# clock.net
KiCad netlist of a schematic drawn in EAGLE
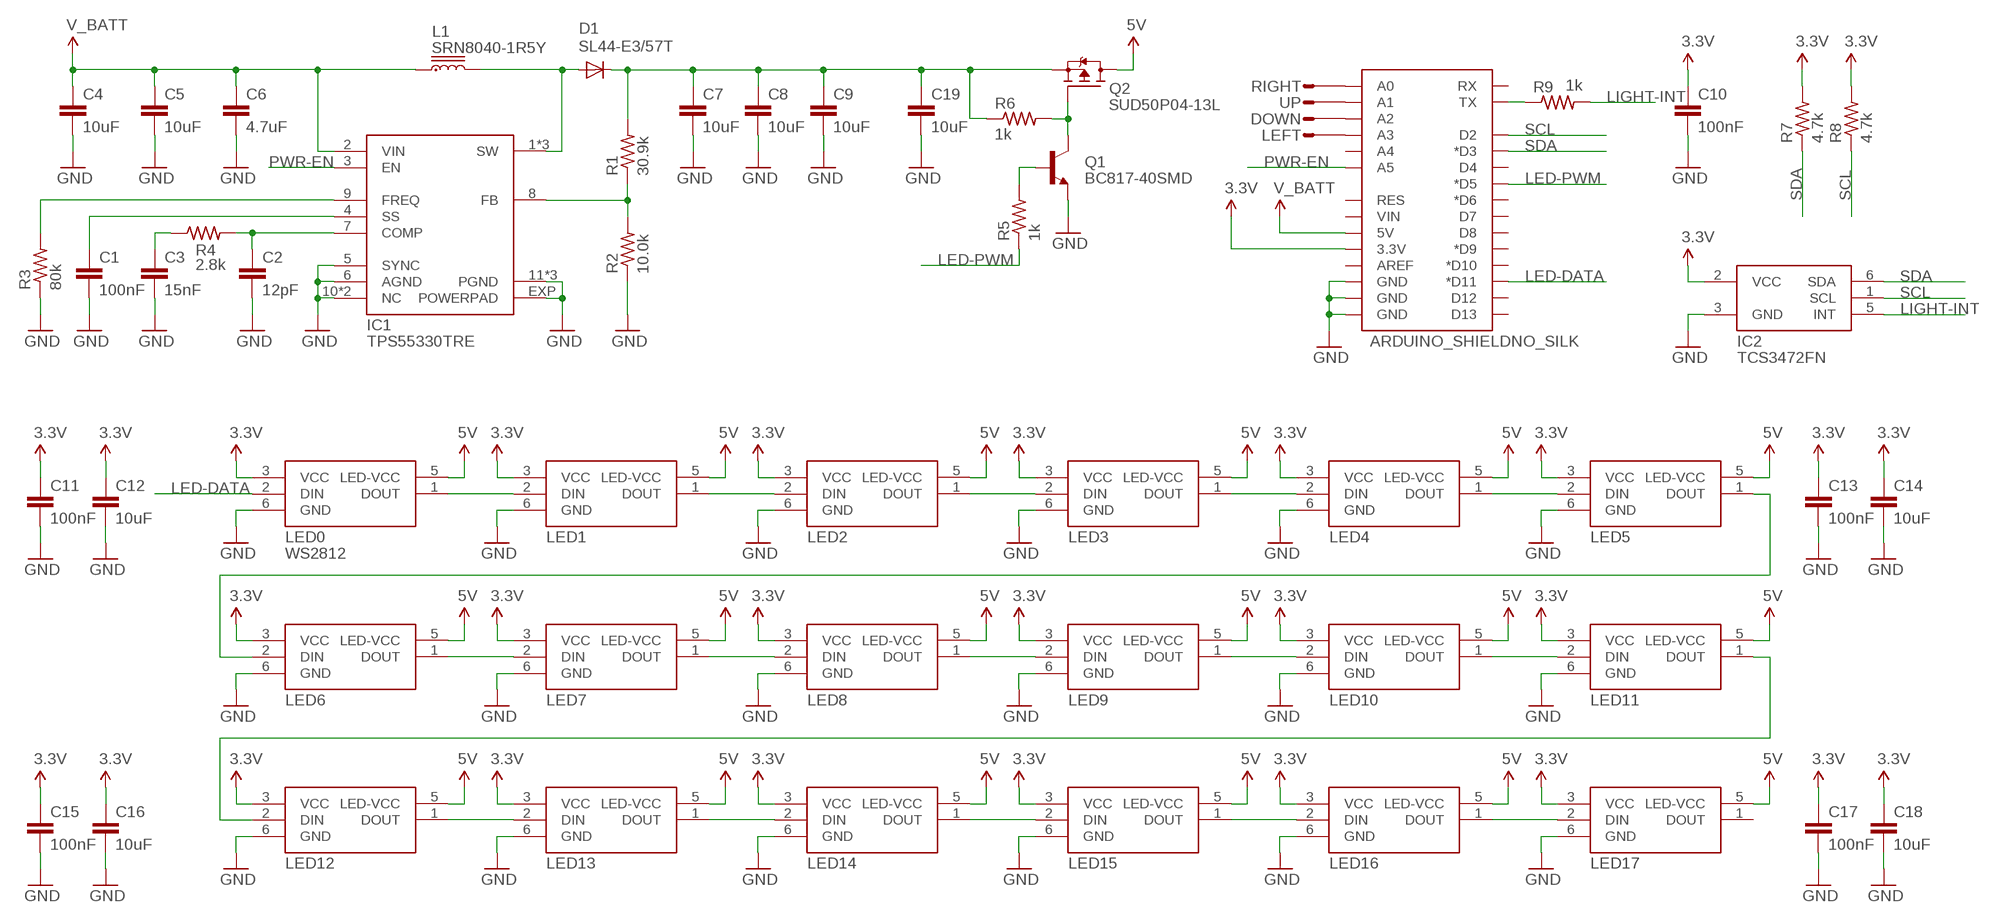
[diagram p0: schematic, sheet 1]

(export (version "E")
  (design (tool "Eeschema 10.0.6"))
  (components
    (comp (ref "C1")
      (value "100nF")
      (footprint "eagle-import:C0603K")
      (libsource (lib "eagle-import") (part "C-EUC0603K"))
    )
    (comp (ref "C2")
      (value "12pF")
      (footprint "eagle-import:C0603K")
      (libsource (lib "eagle-import") (part "C-EUC0603K"))
    )
    (comp (ref "C3")
      (value "15nF")
      (footprint "eagle-import:C0603K")
      (libsource (lib "eagle-import") (part "C-EUC0603K"))
    )
    (comp (ref "C4")
      (value "10uF")
      (footprint "eagle-import:C1206K")
      (libsource (lib "eagle-import") (part "C-EUC1206K"))
    )
    (comp (ref "C5")
      (value "10uF")
      (footprint "eagle-import:C1206K")
      (libsource (lib "eagle-import") (part "C-EUC1206K"))
    )
    (comp (ref "C6")
      (value "4.7uF")
      (footprint "eagle-import:C0805K")
      (libsource (lib "eagle-import") (part "C-EUC0805K"))
    )
    (comp (ref "C7")
      (value "10uF")
      (footprint "eagle-import:C1206K")
      (libsource (lib "eagle-import") (part "C-EUC1206K"))
    )
    (comp (ref "C8")
      (value "10uF")
      (footprint "eagle-import:C1206K")
      (libsource (lib "eagle-import") (part "C-EUC1206K"))
    )
    (comp (ref "C9")
      (value "10uF")
      (footprint "eagle-import:C1206K")
      (libsource (lib "eagle-import") (part "C-EUC1206K"))
    )
    (comp (ref "C10")
      (value "100nF")
      (footprint "eagle-import:C0603K")
      (libsource (lib "eagle-import") (part "C-EUC0603K"))
    )
    (comp (ref "C11")
      (value "100nF")
      (footprint "eagle-import:C0603K")
      (libsource (lib "eagle-import") (part "C-EUC0603K"))
    )
    (comp (ref "C12")
      (value "10uF")
      (footprint "eagle-import:C1206K")
      (libsource (lib "eagle-import") (part "C-EUC1206K"))
    )
    (comp (ref "C13")
      (value "100nF")
      (footprint "eagle-import:C0603K")
      (libsource (lib "eagle-import") (part "C-EUC0603K"))
    )
    (comp (ref "C14")
      (value "10uF")
      (footprint "eagle-import:C1206K")
      (libsource (lib "eagle-import") (part "C-EUC1206K"))
    )
    (comp (ref "C15")
      (value "100nF")
      (footprint "eagle-import:C0603K")
      (libsource (lib "eagle-import") (part "C-EUC0603K"))
    )
    (comp (ref "C16")
      (value "10uF")
      (footprint "eagle-import:C1206K")
      (libsource (lib "eagle-import") (part "C-EUC1206K"))
    )
    (comp (ref "C17")
      (value "100nF")
      (footprint "eagle-import:C0603K")
      (libsource (lib "eagle-import") (part "C-EUC0603K"))
    )
    (comp (ref "C18")
      (value "10uF")
      (footprint "eagle-import:C1206K")
      (libsource (lib "eagle-import") (part "C-EUC1206K"))
    )
    (comp (ref "C19")
      (value "10uF")
      (footprint "eagle-import:C1206K")
      (libsource (lib "eagle-import") (part "C-EUC1206K"))
    )
    (comp (ref "CN1")
      (value "ARDUINO_SHIELDNO_SILK")
      (footprint "eagle-import:DUEMILANOVE_VIAS")
      (libsource (lib "eagle-import") (part "ARDUINO_SHIELDNO_SILK"))
    )
    (comp (ref "D1")
      (value "SL44-E3/57T")
      (footprint "eagle-import:SMC")
      (libsource (lib "eagle-import") (part "DIODE-SMC"))
    )
    (comp (ref "DOWN")
      (value "CAP-PAD15MM")
      (footprint "eagle-import:CAP-PAD-15MM")
      (libsource (lib "eagle-import") (part "CAP-PAD15MM"))
    )
    (comp (ref "IC1")
      (value "TPS55330TRE")
      (footprint "eagle-import:QFN16")
      (libsource (lib "eagle-import") (part "TPS55330TRE"))
    )
    (comp (ref "IC2")
      (value "TCS3472FN")
      (footprint "eagle-import:DFN-6")
      (libsource (lib "eagle-import") (part "TCS3472FN"))
    )
    (comp (ref "L1")
      (value "SRN8040-1R5Y")
      (footprint "eagle-import:SRN8040")
      (libsource (lib "eagle-import") (part "SRN8040"))
    )
    (comp (ref "LED0")
      (value "WS2812")
      (footprint "eagle-import:LED-TRICOLOR-5050-IC")
      (libsource (lib "eagle-import") (part "WS2812"))
    )
    (comp (ref "LED1")
      (value "WS2812")
      (footprint "eagle-import:LED-TRICOLOR-5050-IC")
      (libsource (lib "eagle-import") (part "WS2812"))
    )
    (comp (ref "LED2")
      (value "WS2812")
      (footprint "eagle-import:LED-TRICOLOR-5050-IC")
      (libsource (lib "eagle-import") (part "WS2812"))
    )
    (comp (ref "LED3")
      (value "WS2812")
      (footprint "eagle-import:LED-TRICOLOR-5050-IC")
      (libsource (lib "eagle-import") (part "WS2812"))
    )
    (comp (ref "LED4")
      (value "WS2812")
      (footprint "eagle-import:LED-TRICOLOR-5050-IC")
      (libsource (lib "eagle-import") (part "WS2812"))
    )
    (comp (ref "LED5")
      (value "WS2812")
      (footprint "eagle-import:LED-TRICOLOR-5050-IC")
      (libsource (lib "eagle-import") (part "WS2812"))
    )
    (comp (ref "LED6")
      (value "WS2812")
      (footprint "eagle-import:LED-TRICOLOR-5050-IC")
      (libsource (lib "eagle-import") (part "WS2812"))
    )
    (comp (ref "LED7")
      (value "WS2812")
      (footprint "eagle-import:LED-TRICOLOR-5050-IC")
      (libsource (lib "eagle-import") (part "WS2812"))
    )
    (comp (ref "LED8")
      (value "WS2812")
      (footprint "eagle-import:LED-TRICOLOR-5050-IC")
      (libsource (lib "eagle-import") (part "WS2812"))
    )
    (comp (ref "LED9")
      (value "WS2812")
      (footprint "eagle-import:LED-TRICOLOR-5050-IC")
      (libsource (lib "eagle-import") (part "WS2812"))
    )
    (comp (ref "LED10")
      (value "WS2812")
      (footprint "eagle-import:LED-TRICOLOR-5050-IC")
      (libsource (lib "eagle-import") (part "WS2812"))
    )
    (comp (ref "LED11")
      (value "WS2812")
      (footprint "eagle-import:LED-TRICOLOR-5050-IC")
      (libsource (lib "eagle-import") (part "WS2812"))
    )
    (comp (ref "LED12")
      (value "WS2812")
      (footprint "eagle-import:LED-TRICOLOR-5050-IC")
      (libsource (lib "eagle-import") (part "WS2812"))
    )
    (comp (ref "LED13")
      (value "WS2812")
      (footprint "eagle-import:LED-TRICOLOR-5050-IC")
      (libsource (lib "eagle-import") (part "WS2812"))
    )
    (comp (ref "LED14")
      (value "WS2812")
      (footprint "eagle-import:LED-TRICOLOR-5050-IC")
      (libsource (lib "eagle-import") (part "WS2812"))
    )
    (comp (ref "LED15")
      (value "WS2812")
      (footprint "eagle-import:LED-TRICOLOR-5050-IC")
      (libsource (lib "eagle-import") (part "WS2812"))
    )
    (comp (ref "LED16")
      (value "WS2812")
      (footprint "eagle-import:LED-TRICOLOR-5050-IC")
      (libsource (lib "eagle-import") (part "WS2812"))
    )
    (comp (ref "LED17")
      (value "WS2812")
      (footprint "eagle-import:LED-TRICOLOR-5050-IC")
      (libsource (lib "eagle-import") (part "WS2812"))
    )
    (comp (ref "LEFT")
      (value "CAP-PAD15MM")
      (footprint "eagle-import:CAP-PAD-15MM")
      (libsource (lib "eagle-import") (part "CAP-PAD15MM"))
    )
    (comp (ref "Q1")
      (value "BC817-40SMD")
      (footprint "eagle-import:SOT23-BEC")
      (libsource (lib "eagle-import") (part "BC817SMD-40"))
    )
    (comp (ref "Q2")
      (value "SUD50P04-13L")
      (footprint "eagle-import:TO252")
      (libsource (lib "eagle-import") (part "FDD4141TO252"))
    )
    (comp (ref "R1")
      (value "30.9k")
      (footprint "eagle-import:R0603")
      (libsource (lib "eagle-import") (part "R-US_R0603"))
    )
    (comp (ref "R2")
      (value "10.0k")
      (footprint "eagle-import:R0603")
      (libsource (lib "eagle-import") (part "R-US_R0603"))
    )
    (comp (ref "R3")
      (value "80k")
      (footprint "eagle-import:R0603")
      (libsource (lib "eagle-import") (part "R-US_R0603"))
    )
    (comp (ref "R4")
      (value "2.8k")
      (footprint "eagle-import:R0603")
      (libsource (lib "eagle-import") (part "R-US_R0603"))
    )
    (comp (ref "R5")
      (value "1k")
      (footprint "eagle-import:R0603")
      (libsource (lib "eagle-import") (part "R-US_R0603"))
    )
    (comp (ref "R6")
      (value "1k")
      (footprint "eagle-import:R0603")
      (libsource (lib "eagle-import") (part "R-US_R0603"))
    )
    (comp (ref "R7")
      (value "4.7k")
      (footprint "eagle-import:R0603")
      (libsource (lib "eagle-import") (part "R-US_R0603"))
    )
    (comp (ref "R8")
      (value "4.7k")
      (footprint "eagle-import:R0603")
      (libsource (lib "eagle-import") (part "R-US_R0603"))
    )
    (comp (ref "R9")
      (value "1k")
      (footprint "eagle-import:R0603")
      (libsource (lib "eagle-import") (part "R-US_R0603"))
    )
    (comp (ref "RIGHT")
      (value "CAP-PAD15MM")
      (footprint "eagle-import:CAP-PAD-15MM")
      (libsource (lib "eagle-import") (part "CAP-PAD15MM"))
    )
    (comp (ref "UP")
      (value "CAP-PAD15MM")
      (footprint "eagle-import:CAP-PAD-15MM")
      (libsource (lib "eagle-import") (part "CAP-PAD15MM"))
    )
  )
  (nets
    (net (code "1") (name "/LED-DATA") (class "Default")
      (node (ref "CN1") (pin "D11") (pinfunction "*D11_D11") (pintype "bidirectional"))
      (node (ref "LED0") (pin "2") (pinfunction "DIN_2") (pintype "input"))
    )
    (net (code "2") (name "/LED-PWM") (class "Default")
      (node (ref "CN1") (pin "D5") (pinfunction "*D5_D5") (pintype "bidirectional"))
      (node (ref "R5") (pin "1") (pinfunction "1_1") (pintype "passive"))
    )
    (net (code "3") (name "/LIGHT-INT") (class "Default")
      (node (ref "IC2") (pin "5") (pinfunction "INT_5") (pintype "output"))
      (node (ref "R9") (pin "2") (pinfunction "2_2") (pintype "passive"))
    )
    (net (code "4") (name "/PWR-EN") (class "Default")
      (node (ref "CN1") (pin "A5") (pinfunction "A5_A5") (pintype "bidirectional"))
      (node (ref "IC1") (pin "3") (pinfunction "EN_3") (pintype "input"))
    )
    (net (code "5") (name "/SCL") (class "Default")
      (node (ref "CN1") (pin "D2") (pinfunction "D2_D2") (pintype "bidirectional"))
      (node (ref "IC2") (pin "1") (pinfunction "SCL_1") (pintype "bidirectional"))
      (node (ref "R8") (pin "1") (pinfunction "1_1") (pintype "passive"))
    )
    (net (code "6") (name "/SDA") (class "Default")
      (node (ref "CN1") (pin "D3") (pinfunction "*D3_D3") (pintype "bidirectional"))
      (node (ref "IC2") (pin "6") (pinfunction "SDA_6") (pintype "bidirectional"))
      (node (ref "R7") (pin "1") (pinfunction "1_1") (pintype "passive"))
    )
    (net (code "7") (name "3.3V") (class "Default")
      (node (ref "C10") (pin "1") (pinfunction "1_1") (pintype "passive"))
      (node (ref "C11") (pin "1") (pinfunction "1_1") (pintype "passive"))
      (node (ref "C12") (pin "1") (pinfunction "1_1") (pintype "passive"))
      (node (ref "C13") (pin "1") (pinfunction "1_1") (pintype "passive"))
      (node (ref "C14") (pin "1") (pinfunction "1_1") (pintype "passive"))
      (node (ref "C15") (pin "1") (pinfunction "1_1") (pintype "passive"))
      (node (ref "C16") (pin "1") (pinfunction "1_1") (pintype "passive"))
      (node (ref "C17") (pin "1") (pinfunction "1_1") (pintype "passive"))
      (node (ref "C18") (pin "1") (pinfunction "1_1") (pintype "passive"))
      (node (ref "CN1") (pin "3.3V") (pinfunction "3.3V_3.3V") (pintype "bidirectional"))
      (node (ref "IC2") (pin "2") (pinfunction "VCC_2") (pintype "power_in"))
      (node (ref "LED0") (pin "3") (pinfunction "VCC_3") (pintype "power_in"))
      (node (ref "LED1") (pin "3") (pinfunction "VCC_3") (pintype "power_in"))
      (node (ref "LED10") (pin "3") (pinfunction "VCC_3") (pintype "power_in"))
      (node (ref "LED11") (pin "3") (pinfunction "VCC_3") (pintype "power_in"))
      (node (ref "LED12") (pin "3") (pinfunction "VCC_3") (pintype "power_in"))
      (node (ref "LED13") (pin "3") (pinfunction "VCC_3") (pintype "power_in"))
      (node (ref "LED14") (pin "3") (pinfunction "VCC_3") (pintype "power_in"))
      (node (ref "LED15") (pin "3") (pinfunction "VCC_3") (pintype "power_in"))
      (node (ref "LED16") (pin "3") (pinfunction "VCC_3") (pintype "power_in"))
      (node (ref "LED17") (pin "3") (pinfunction "VCC_3") (pintype "power_in"))
      (node (ref "LED2") (pin "3") (pinfunction "VCC_3") (pintype "power_in"))
      (node (ref "LED3") (pin "3") (pinfunction "VCC_3") (pintype "power_in"))
      (node (ref "LED4") (pin "3") (pinfunction "VCC_3") (pintype "power_in"))
      (node (ref "LED5") (pin "3") (pinfunction "VCC_3") (pintype "power_in"))
      (node (ref "LED6") (pin "3") (pinfunction "VCC_3") (pintype "power_in"))
      (node (ref "LED7") (pin "3") (pinfunction "VCC_3") (pintype "power_in"))
      (node (ref "LED8") (pin "3") (pinfunction "VCC_3") (pintype "power_in"))
      (node (ref "LED9") (pin "3") (pinfunction "VCC_3") (pintype "power_in"))
      (node (ref "R7") (pin "2") (pinfunction "2_2") (pintype "passive"))
      (node (ref "R8") (pin "2") (pinfunction "2_2") (pintype "passive"))
    )
    (net (code "8") (name "5V") (class "Default")
      (node (ref "LED0") (pin "5") (pinfunction "LED-VCC_5") (pintype "power_in"))
      (node (ref "LED1") (pin "5") (pinfunction "LED-VCC_5") (pintype "power_in"))
      (node (ref "LED10") (pin "5") (pinfunction "LED-VCC_5") (pintype "power_in"))
      (node (ref "LED11") (pin "5") (pinfunction "LED-VCC_5") (pintype "power_in"))
      (node (ref "LED12") (pin "5") (pinfunction "LED-VCC_5") (pintype "power_in"))
      (node (ref "LED13") (pin "5") (pinfunction "LED-VCC_5") (pintype "power_in"))
      (node (ref "LED14") (pin "5") (pinfunction "LED-VCC_5") (pintype "power_in"))
      (node (ref "LED15") (pin "5") (pinfunction "LED-VCC_5") (pintype "power_in"))
      (node (ref "LED16") (pin "5") (pinfunction "LED-VCC_5") (pintype "power_in"))
      (node (ref "LED17") (pin "5") (pinfunction "LED-VCC_5") (pintype "power_in"))
      (node (ref "LED2") (pin "5") (pinfunction "LED-VCC_5") (pintype "power_in"))
      (node (ref "LED3") (pin "5") (pinfunction "LED-VCC_5") (pintype "power_in"))
      (node (ref "LED4") (pin "5") (pinfunction "LED-VCC_5") (pintype "power_in"))
      (node (ref "LED5") (pin "5") (pinfunction "LED-VCC_5") (pintype "power_in"))
      (node (ref "LED6") (pin "5") (pinfunction "LED-VCC_5") (pintype "power_in"))
      (node (ref "LED7") (pin "5") (pinfunction "LED-VCC_5") (pintype "power_in"))
      (node (ref "LED8") (pin "5") (pinfunction "LED-VCC_5") (pintype "power_in"))
      (node (ref "LED9") (pin "5") (pinfunction "LED-VCC_5") (pintype "power_in"))
      (node (ref "Q2") (pin "3") (pinfunction "D_3") (pintype "passive"))
    )
    (net (code "9") (name "GND") (class "Default")
      (node (ref "C1") (pin "2") (pinfunction "2_2") (pintype "passive"))
      (node (ref "C10") (pin "2") (pinfunction "2_2") (pintype "passive"))
      (node (ref "C11") (pin "2") (pinfunction "2_2") (pintype "passive"))
      (node (ref "C12") (pin "2") (pinfunction "2_2") (pintype "passive"))
      (node (ref "C13") (pin "2") (pinfunction "2_2") (pintype "passive"))
      (node (ref "C14") (pin "2") (pinfunction "2_2") (pintype "passive"))
      (node (ref "C15") (pin "2") (pinfunction "2_2") (pintype "passive"))
      (node (ref "C16") (pin "2") (pinfunction "2_2") (pintype "passive"))
      (node (ref "C17") (pin "2") (pinfunction "2_2") (pintype "passive"))
      (node (ref "C18") (pin "2") (pinfunction "2_2") (pintype "passive"))
      (node (ref "C19") (pin "2") (pinfunction "2_2") (pintype "passive"))
      (node (ref "C2") (pin "2") (pinfunction "2_2") (pintype "passive"))
      (node (ref "C3") (pin "2") (pinfunction "2_2") (pintype "passive"))
      (node (ref "C4") (pin "2") (pinfunction "2_2") (pintype "passive"))
      (node (ref "C5") (pin "2") (pinfunction "2_2") (pintype "passive"))
      (node (ref "C6") (pin "2") (pinfunction "2_2") (pintype "passive"))
      (node (ref "C7") (pin "2") (pinfunction "2_2") (pintype "passive"))
      (node (ref "C8") (pin "2") (pinfunction "2_2") (pintype "passive"))
      (node (ref "C9") (pin "2") (pinfunction "2_2") (pintype "passive"))
      (node (ref "CN1") (pin "GND@0") (pinfunction "GND_GND@0") (pintype "bidirectional"))
      (node (ref "CN1") (pin "GND@1") (pinfunction "GND_GND@1") (pintype "bidirectional"))
      (node (ref "CN1") (pin "GND@2") (pinfunction "GND_GND@2") (pintype "bidirectional"))
      (node (ref "IC1") (pin "10") (pinfunction "NC_10") (pintype "power_in"))
      (node (ref "IC1") (pin "11") (pinfunction "PGND_11") (pintype "input"))
      (node (ref "IC1") (pin "12") (pinfunction "PGND_12") (pintype "input"))
      (node (ref "IC1") (pin "13") (pinfunction "PGND_13") (pintype "input"))
      (node (ref "IC1") (pin "14") (pinfunction "NC_14") (pintype "power_in"))
      (node (ref "IC1") (pin "5") (pinfunction "SYNC_5") (pintype "input"))
      (node (ref "IC1") (pin "6") (pinfunction "AGND_6") (pintype "power_in"))
      (node (ref "IC1") (pin "EXP") (pinfunction "POWERPAD_EXP") (pintype "power_in"))
      (node (ref "IC2") (pin "3") (pinfunction "GND_3") (pintype "power_in"))
      (node (ref "LED0") (pin "6") (pinfunction "GND_6") (pintype "power_in"))
      (node (ref "LED1") (pin "6") (pinfunction "GND_6") (pintype "power_in"))
      (node (ref "LED10") (pin "6") (pinfunction "GND_6") (pintype "power_in"))
      (node (ref "LED11") (pin "6") (pinfunction "GND_6") (pintype "power_in"))
      (node (ref "LED12") (pin "6") (pinfunction "GND_6") (pintype "power_in"))
      (node (ref "LED13") (pin "6") (pinfunction "GND_6") (pintype "power_in"))
      (node (ref "LED14") (pin "6") (pinfunction "GND_6") (pintype "power_in"))
      (node (ref "LED15") (pin "6") (pinfunction "GND_6") (pintype "power_in"))
      (node (ref "LED16") (pin "6") (pinfunction "GND_6") (pintype "power_in"))
      (node (ref "LED17") (pin "6") (pinfunction "GND_6") (pintype "power_in"))
      (node (ref "LED2") (pin "6") (pinfunction "GND_6") (pintype "power_in"))
      (node (ref "LED3") (pin "6") (pinfunction "GND_6") (pintype "power_in"))
      (node (ref "LED4") (pin "6") (pinfunction "GND_6") (pintype "power_in"))
      (node (ref "LED5") (pin "6") (pinfunction "GND_6") (pintype "power_in"))
      (node (ref "LED6") (pin "6") (pinfunction "GND_6") (pintype "power_in"))
      (node (ref "LED7") (pin "6") (pinfunction "GND_6") (pintype "power_in"))
      (node (ref "LED8") (pin "6") (pinfunction "GND_6") (pintype "power_in"))
      (node (ref "LED9") (pin "6") (pinfunction "GND_6") (pintype "power_in"))
      (node (ref "Q1") (pin "E") (pinfunction "E_E") (pintype "passive"))
      (node (ref "R2") (pin "1") (pinfunction "1_1") (pintype "passive"))
      (node (ref "R3") (pin "1") (pinfunction "1_1") (pintype "passive"))
    )
    (net (code "10") (name "Net-(C3-Pad1)") (class "Default")
      (node (ref "C3") (pin "1") (pinfunction "1_1") (pintype "passive"))
      (node (ref "R4") (pin "1") (pinfunction "1_1") (pintype "passive"))
    )
    (net (code "11") (name "Net-(CN1-PadTX)") (class "Default")
      (node (ref "CN1") (pin "TX") (pinfunction "TX_TX") (pintype "bidirectional"))
      (node (ref "R9") (pin "1") (pinfunction "1_1") (pintype "passive"))
    )
    (net (code "12") (name "Net-(DOWN-1)") (class "Default")
      (node (ref "CN1") (pin "A2") (pinfunction "A2_A2") (pintype "bidirectional"))
      (node (ref "DOWN") (pin "P$1") (pinfunction "1_P$1") (pintype "passive"))
    )
    (net (code "13") (name "Net-(IC1-COMP)") (class "Default")
      (node (ref "C2") (pin "1") (pinfunction "1_1") (pintype "passive"))
      (node (ref "IC1") (pin "7") (pinfunction "COMP_7") (pintype "bidirectional"))
      (node (ref "R4") (pin "2") (pinfunction "2_2") (pintype "passive"))
    )
    (net (code "14") (name "Net-(IC1-FB)") (class "Default")
      (node (ref "IC1") (pin "8") (pinfunction "FB_8") (pintype "input"))
      (node (ref "R1") (pin "1") (pinfunction "1_1") (pintype "passive"))
      (node (ref "R2") (pin "2") (pinfunction "2_2") (pintype "passive"))
    )
    (net (code "15") (name "Net-(IC1-FREQ)") (class "Default")
      (node (ref "IC1") (pin "9") (pinfunction "FREQ_9") (pintype "bidirectional"))
      (node (ref "R3") (pin "2") (pinfunction "2_2") (pintype "passive"))
    )
    (net (code "16") (name "Net-(IC1-SS)") (class "Default")
      (node (ref "C1") (pin "1") (pinfunction "1_1") (pintype "passive"))
      (node (ref "IC1") (pin "4") (pinfunction "SS_4") (pintype "bidirectional"))
    )
    (net (code "17") (name "Net-(L1-2)") (class "Default")
      (node (ref "D1") (pin "A") (pinfunction "A_A") (pintype "passive"))
      (node (ref "IC1") (pin "1") (pinfunction "SW_1") (pintype "power_in"))
      (node (ref "IC1") (pin "15") (pinfunction "SW_15") (pintype "power_in"))
      (node (ref "IC1") (pin "16") (pinfunction "SW_16") (pintype "power_in"))
      (node (ref "L1") (pin "P$2") (pinfunction "2_P$2") (pintype "passive"))
    )
    (net (code "18") (name "Net-(LED0-DOUT)") (class "Default")
      (node (ref "LED0") (pin "1") (pinfunction "DOUT_1") (pintype "output"))
      (node (ref "LED1") (pin "2") (pinfunction "DIN_2") (pintype "input"))
    )
    (net (code "19") (name "Net-(LED1-DOUT)") (class "Default")
      (node (ref "LED1") (pin "1") (pinfunction "DOUT_1") (pintype "output"))
      (node (ref "LED2") (pin "2") (pinfunction "DIN_2") (pintype "input"))
    )
    (net (code "20") (name "Net-(LED2-DOUT)") (class "Default")
      (node (ref "LED2") (pin "1") (pinfunction "DOUT_1") (pintype "output"))
      (node (ref "LED3") (pin "2") (pinfunction "DIN_2") (pintype "input"))
    )
    (net (code "21") (name "Net-(LED3-DOUT)") (class "Default")
      (node (ref "LED3") (pin "1") (pinfunction "DOUT_1") (pintype "output"))
      (node (ref "LED4") (pin "2") (pinfunction "DIN_2") (pintype "input"))
    )
    (net (code "22") (name "Net-(LED4-DOUT)") (class "Default")
      (node (ref "LED4") (pin "1") (pinfunction "DOUT_1") (pintype "output"))
      (node (ref "LED5") (pin "2") (pinfunction "DIN_2") (pintype "input"))
    )
    (net (code "23") (name "Net-(LED5-DOUT)") (class "Default")
      (node (ref "LED5") (pin "1") (pinfunction "DOUT_1") (pintype "output"))
      (node (ref "LED6") (pin "2") (pinfunction "DIN_2") (pintype "input"))
    )
    (net (code "24") (name "Net-(LED6-DOUT)") (class "Default")
      (node (ref "LED6") (pin "1") (pinfunction "DOUT_1") (pintype "output"))
      (node (ref "LED7") (pin "2") (pinfunction "DIN_2") (pintype "input"))
    )
    (net (code "25") (name "Net-(LED7-DOUT)") (class "Default")
      (node (ref "LED7") (pin "1") (pinfunction "DOUT_1") (pintype "output"))
      (node (ref "LED8") (pin "2") (pinfunction "DIN_2") (pintype "input"))
    )
    (net (code "26") (name "Net-(LED8-DOUT)") (class "Default")
      (node (ref "LED8") (pin "1") (pinfunction "DOUT_1") (pintype "output"))
      (node (ref "LED9") (pin "2") (pinfunction "DIN_2") (pintype "input"))
    )
    (net (code "27") (name "Net-(LED10-DIN)") (class "Default")
      (node (ref "LED10") (pin "2") (pinfunction "DIN_2") (pintype "input"))
      (node (ref "LED9") (pin "1") (pinfunction "DOUT_1") (pintype "output"))
    )
    (net (code "28") (name "Net-(LED10-DOUT)") (class "Default")
      (node (ref "LED10") (pin "1") (pinfunction "DOUT_1") (pintype "output"))
      (node (ref "LED11") (pin "2") (pinfunction "DIN_2") (pintype "input"))
    )
    (net (code "29") (name "Net-(LED11-DOUT)") (class "Default")
      (node (ref "LED11") (pin "1") (pinfunction "DOUT_1") (pintype "output"))
      (node (ref "LED12") (pin "2") (pinfunction "DIN_2") (pintype "input"))
    )
    (net (code "30") (name "Net-(LED12-DOUT)") (class "Default")
      (node (ref "LED12") (pin "1") (pinfunction "DOUT_1") (pintype "output"))
      (node (ref "LED13") (pin "2") (pinfunction "DIN_2") (pintype "input"))
    )
    (net (code "31") (name "Net-(LED13-DOUT)") (class "Default")
      (node (ref "LED13") (pin "1") (pinfunction "DOUT_1") (pintype "output"))
      (node (ref "LED14") (pin "2") (pinfunction "DIN_2") (pintype "input"))
    )
    (net (code "32") (name "Net-(LED14-DOUT)") (class "Default")
      (node (ref "LED14") (pin "1") (pinfunction "DOUT_1") (pintype "output"))
      (node (ref "LED15") (pin "2") (pinfunction "DIN_2") (pintype "input"))
    )
    (net (code "33") (name "Net-(LED15-DOUT)") (class "Default")
      (node (ref "LED15") (pin "1") (pinfunction "DOUT_1") (pintype "output"))
      (node (ref "LED16") (pin "2") (pinfunction "DIN_2") (pintype "input"))
    )
    (net (code "34") (name "Net-(LED16-DOUT)") (class "Default")
      (node (ref "LED16") (pin "1") (pinfunction "DOUT_1") (pintype "output"))
      (node (ref "LED17") (pin "2") (pinfunction "DIN_2") (pintype "input"))
    )
    (net (code "35") (name "Net-(LEFT-1)") (class "Default")
      (node (ref "CN1") (pin "A3") (pinfunction "A3_A3") (pintype "bidirectional"))
      (node (ref "LEFT") (pin "P$1") (pinfunction "1_P$1") (pintype "passive"))
    )
    (net (code "36") (name "Net-(Q1-PadB)") (class "Default")
      (node (ref "Q1") (pin "B") (pinfunction "B_B") (pintype "passive"))
      (node (ref "R5") (pin "2") (pinfunction "2_2") (pintype "passive"))
    )
    (net (code "37") (name "Net-(Q2-G)") (class "Default")
      (node (ref "Q1") (pin "C") (pinfunction "C_C") (pintype "passive"))
      (node (ref "Q2") (pin "1") (pinfunction "G_1") (pintype "passive"))
      (node (ref "R6") (pin "2") (pinfunction "2_2") (pintype "passive"))
    )
    (net (code "38") (name "Net-(Q2-S)") (class "Default")
      (node (ref "C19") (pin "1") (pinfunction "1_1") (pintype "passive"))
      (node (ref "C7") (pin "1") (pinfunction "1_1") (pintype "passive"))
      (node (ref "C8") (pin "1") (pinfunction "1_1") (pintype "passive"))
      (node (ref "C9") (pin "1") (pinfunction "1_1") (pintype "passive"))
      (node (ref "D1") (pin "C") (pinfunction "C_C") (pintype "passive"))
      (node (ref "Q2") (pin "2") (pinfunction "S_2") (pintype "passive"))
      (node (ref "R1") (pin "2") (pinfunction "2_2") (pintype "passive"))
      (node (ref "R6") (pin "1") (pinfunction "1_1") (pintype "passive"))
    )
    (net (code "39") (name "Net-(RIGHT-1)") (class "Default")
      (node (ref "CN1") (pin "A0") (pinfunction "A0_A0") (pintype "bidirectional"))
      (node (ref "RIGHT") (pin "P$1") (pinfunction "1_P$1") (pintype "passive"))
    )
    (net (code "40") (name "Net-(UP-1)") (class "Default")
      (node (ref "CN1") (pin "A1") (pinfunction "A1_A1") (pintype "bidirectional"))
      (node (ref "UP") (pin "P$1") (pinfunction "1_P$1") (pintype "passive"))
    )
    (net (code "41") (name "V_BATT") (class "Default")
      (node (ref "C4") (pin "1") (pinfunction "1_1") (pintype "passive"))
      (node (ref "C5") (pin "1") (pinfunction "1_1") (pintype "passive"))
      (node (ref "C6") (pin "1") (pinfunction "1_1") (pintype "passive"))
      (node (ref "CN1") (pin "5V") (pinfunction "5V_5V") (pintype "bidirectional"))
      (node (ref "IC1") (pin "2") (pinfunction "VIN_2") (pintype "power_in"))
      (node (ref "L1") (pin "P$1") (pinfunction "1_P$1") (pintype "passive"))
    )
    (net (code "42") (name "unconnected-(CN1-*D6-PadD6)") (class "Default")
      (node (ref "CN1") (pin "D6") (pinfunction "*D6_D6") (pintype "bidirectional"))
    )
    (net (code "43") (name "unconnected-(CN1-*D9-PadD9)") (class "Default")
      (node (ref "CN1") (pin "D9") (pinfunction "*D9_D9") (pintype "bidirectional"))
    )
    (net (code "44") (name "unconnected-(CN1-*D10-PadD10)") (class "Default")
      (node (ref "CN1") (pin "D10") (pinfunction "*D10_D10") (pintype "bidirectional"))
    )
    (net (code "45") (name "unconnected-(CN1-PadA4)") (class "Default")
      (node (ref "CN1") (pin "A4") (pinfunction "A4_A4") (pintype "bidirectional"))
    )
    (net (code "46") (name "unconnected-(CN1-PadAREF)") (class "Default")
      (node (ref "CN1") (pin "AREF") (pinfunction "AREF_AREF") (pintype "bidirectional"))
    )
    (net (code "47") (name "unconnected-(CN1-PadD4)") (class "Default")
      (node (ref "CN1") (pin "D4") (pinfunction "D4_D4") (pintype "bidirectional"))
    )
    (net (code "48") (name "unconnected-(CN1-PadD7)") (class "Default")
      (node (ref "CN1") (pin "D7") (pinfunction "D7_D7") (pintype "bidirectional"))
    )
    (net (code "49") (name "unconnected-(CN1-PadD8)") (class "Default")
      (node (ref "CN1") (pin "D8") (pinfunction "D8_D8") (pintype "bidirectional"))
    )
    (net (code "50") (name "unconnected-(CN1-PadD12)") (class "Default")
      (node (ref "CN1") (pin "D12") (pinfunction "D12_D12") (pintype "bidirectional"))
    )
    (net (code "51") (name "unconnected-(CN1-PadD13)") (class "Default")
      (node (ref "CN1") (pin "D13") (pinfunction "D13_D13") (pintype "bidirectional"))
    )
    (net (code "52") (name "unconnected-(CN1-PadRES)") (class "Default")
      (node (ref "CN1") (pin "RES") (pinfunction "RES_RES") (pintype "bidirectional"))
    )
    (net (code "53") (name "unconnected-(CN1-PadRX)") (class "Default")
      (node (ref "CN1") (pin "RX") (pinfunction "RX_RX") (pintype "bidirectional"))
    )
    (net (code "54") (name "unconnected-(CN1-PadVIN)") (class "Default")
      (node (ref "CN1") (pin "VIN") (pinfunction "VIN_VIN") (pintype "bidirectional"))
    )
    (net (code "55") (name "unconnected-(LED17-DOUT-Pad1)") (class "Default")
      (node (ref "LED17") (pin "1") (pinfunction "DOUT_1") (pintype "output"))
    )
  )
)
